# arduino_phc.net
KiCad netlist of a schematic drawn in Altium Designer
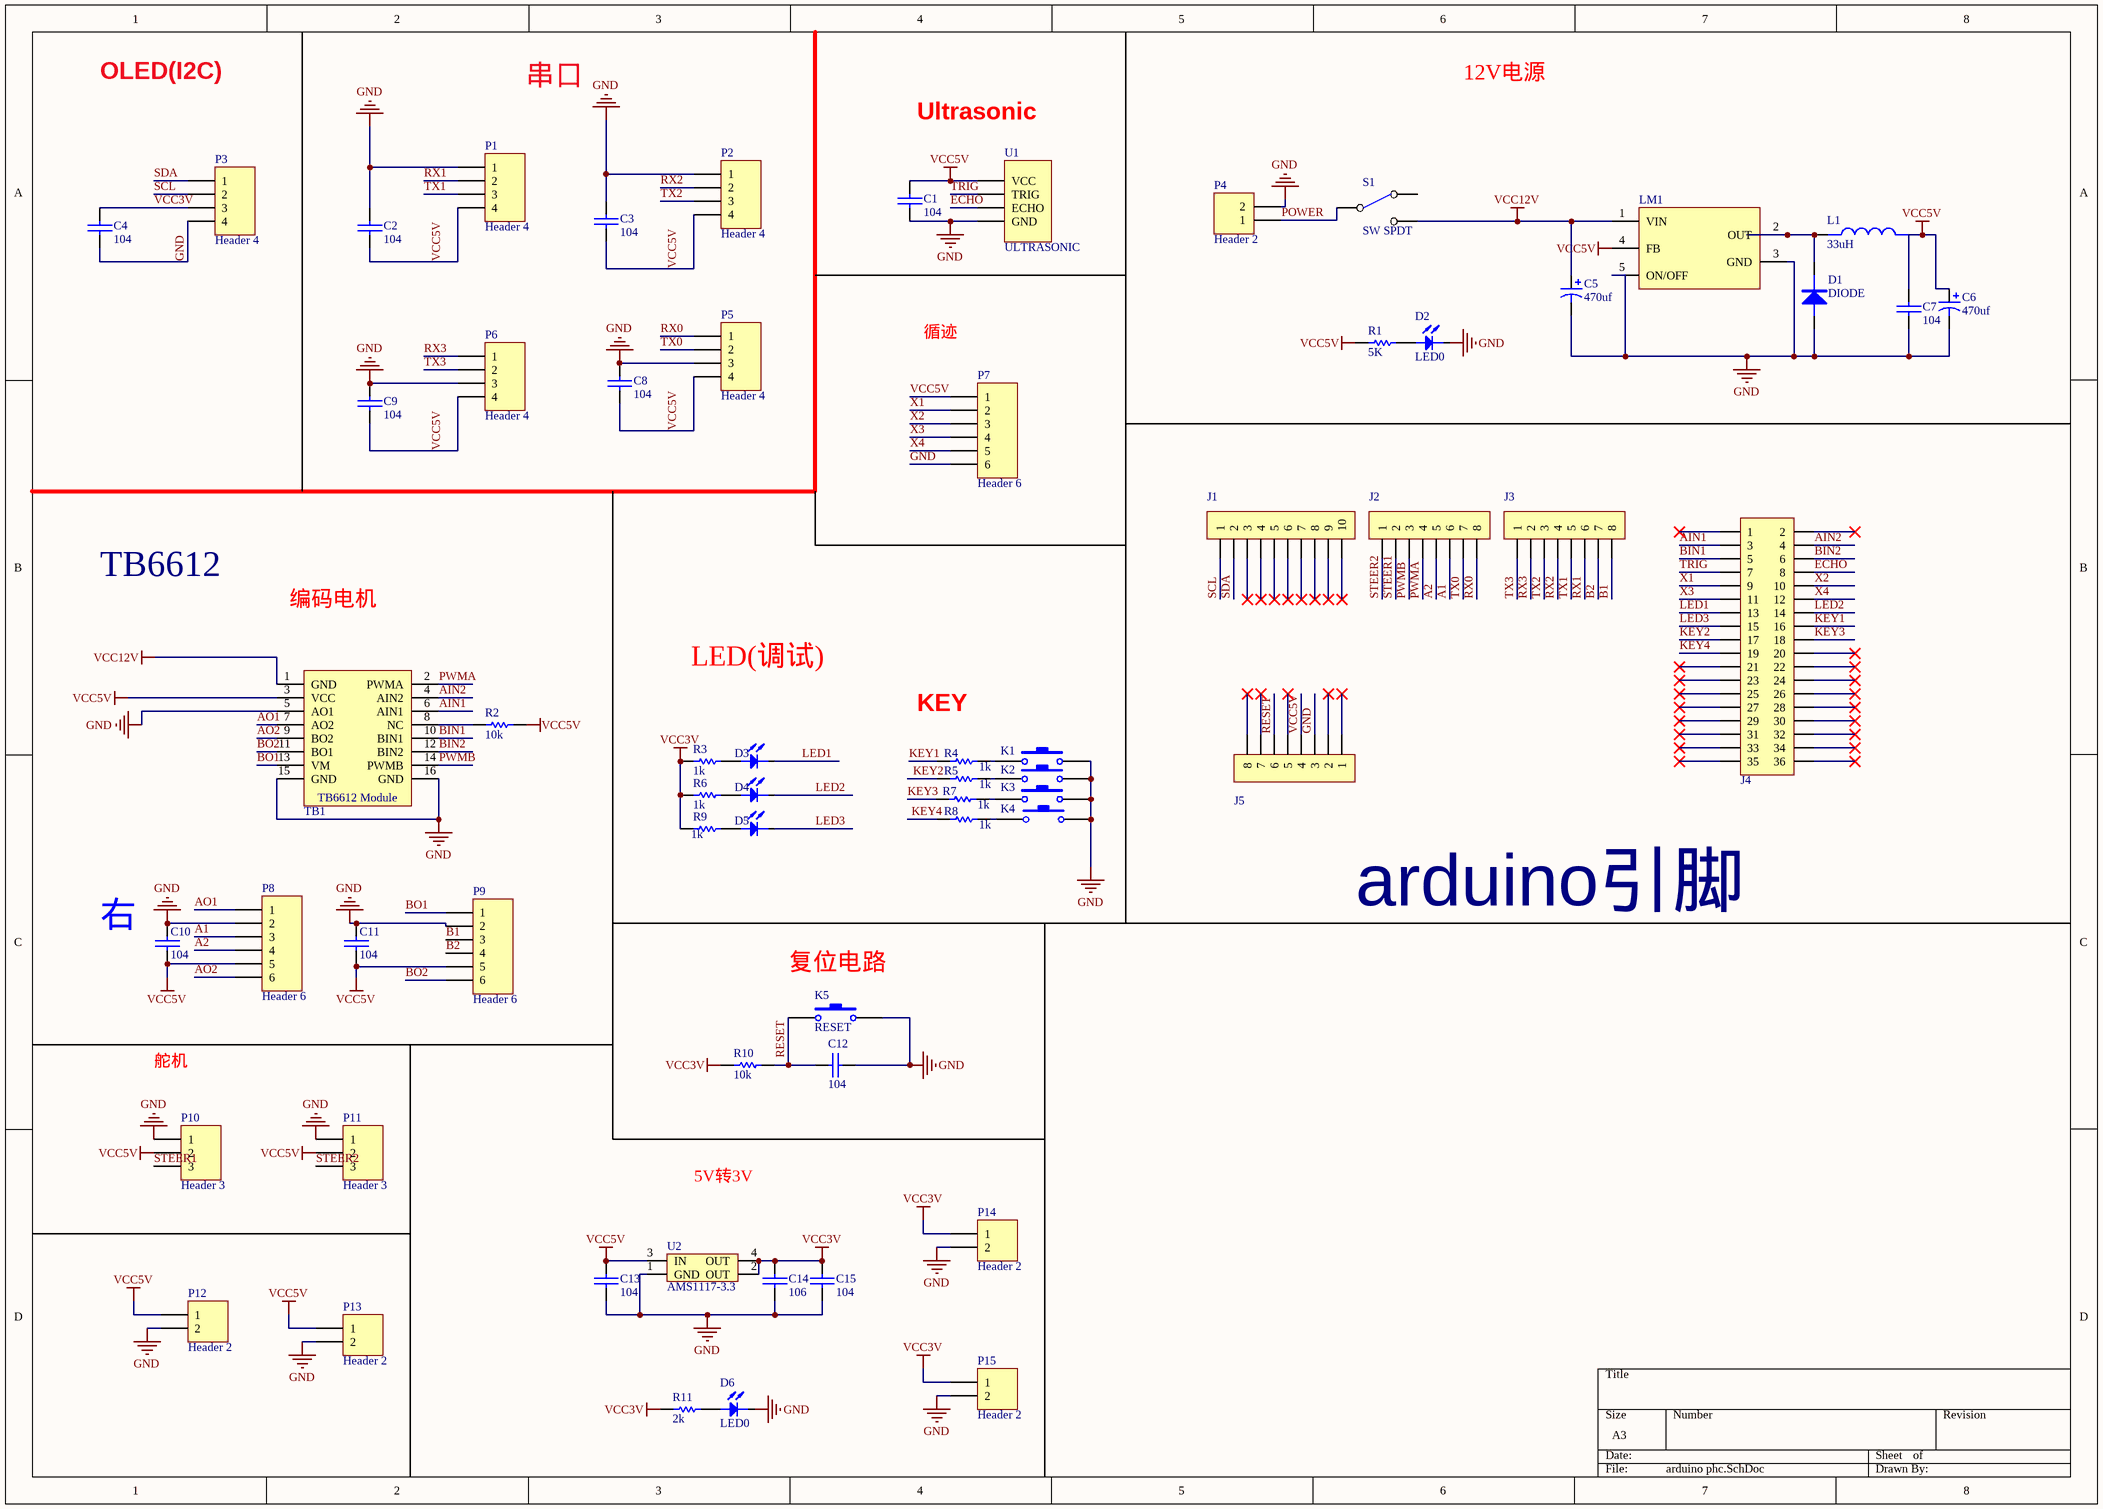
[diagram p0: arduino phc.SchDoc]

(export (version "E")
  (design (tool "Eeschema 10.0.6"))
  (components
    (comp (ref "C1")
      (value "104")
      (footprint "0603_C")
      (fields (field (name "Comment") "CAP"))
      (libsource (lib "MY SCH LIB") (part "CAP"))
    )
    (comp (ref "C2")
      (value "104")
      (footprint "0805_C")
      (fields (field (name "Comment") "CAP"))
      (libsource (lib "MY SCH LIB__JCH") (part "CAP"))
    )
    (comp (ref "C3")
      (value "104")
      (footprint "0805_C")
      (fields (field (name "Comment") "CAP"))
      (libsource (lib "MY SCH LIB__JCH") (part "CAP"))
    )
    (comp (ref "C4")
      (value "104")
      (footprint "0805_C")
      (fields (field (name "Comment") "CAP"))
      (libsource (lib "MY SCH LIB__JCH") (part "CAP"))
    )
    (comp (ref "C5")
      (value "470uf")
      (footprint "CAP-8*16")
      (fields (field (name "Comment") "CAP_HER"))
      (libsource (lib "平衡车") (part "CAP_HER"))
    )
    (comp (ref "C6")
      (value "470uf")
      (footprint "CAP-8*16")
      (fields (field (name "Comment") "CAP_HER"))
      (libsource (lib "平衡车") (part "CAP_HER"))
    )
    (comp (ref "C7")
      (value "104")
      (footprint "0805_C")
      (fields (field (name "Comment") "CAP"))
      (libsource (lib "平衡车") (part "CAP"))
    )
    (comp (ref "C8")
      (value "104")
      (footprint "0805_C")
      (fields (field (name "Comment") "CAP"))
      (libsource (lib "MY SCH LIB__JCH") (part "CAP"))
    )
    (comp (ref "C9")
      (value "104")
      (footprint "0805_C")
      (fields (field (name "Comment") "CAP"))
      (libsource (lib "主控板（32）") (part "CAP"))
    )
    (comp (ref "C10")
      (value "104")
      (footprint "0805_C")
      (fields (field (name "Comment") "CAP"))
      (libsource (lib "MY SCH LIB") (part "CAP"))
    )
    (comp (ref "C11")
      (value "104")
      (footprint "0805_C")
      (fields (field (name "Comment") "CAP"))
      (libsource (lib "MY SCH LIB") (part "CAP"))
    )
    (comp (ref "C12") (value "104") (footprint "0805_C") (libsource (lib "主控板（32）") (part "CAP")))
    (comp (ref "C13")
      (value "104")
      (footprint "0805_C")
      (fields (field (name "Comment") "CAP"))
      (libsource (lib "主控板（32）") (part "CAP"))
    )
    (comp (ref "C14")
      (value "106")
      (footprint "0805_C")
      (fields (field (name "Comment") "CAP"))
      (libsource (lib "主控板（32）") (part "CAP"))
    )
    (comp (ref "C15")
      (value "104")
      (footprint "0805_C")
      (fields (field (name "Comment") "CAP"))
      (libsource (lib "主控板（32）") (part "CAP"))
    )
    (comp (ref "D1") (value "DIODE") (footprint "D1810") (libsource (lib "MY SCH LIB") (part "DIODE")))
    (comp (ref "D2") (value "LED0") (footprint "0805-LED-RED") (libsource (lib "主控板（32）") (part "LED")))
    (comp (ref "D3") (value "LED") (footprint "0805-LED-RED") (libsource (lib "MY SCH LIB") (part "LED")))
    (comp (ref "D4") (value "LED") (footprint "0805-LED-RED") (libsource (lib "MY SCH LIB") (part "LED")))
    (comp (ref "D5") (value "LED") (footprint "0805-LED-RED") (libsource (lib "MY SCH LIB") (part "LED")))
    (comp (ref "D6") (value "LED0") (footprint "0805-LED-RED") (libsource (lib "主控板（32）") (part "LED")))
    (comp (ref "J1")
      (value "HDR-1X10")
      (footprint "HDR2.54-LI-10P")
      (description "10P接插件")
      (libsource (lib "*") (part "Header 10"))
    )
    (comp (ref "J2")
      (value "HDR-1X8")
      (footprint "HDR2.54-LI-8P")
      (description "8P接插件")
      (libsource (lib "") (part "Header 8_1"))
    )
    (comp (ref "J3")
      (value "HDR-1X8")
      (footprint "HDR2.54-LI-8P")
      (description "8P接插件")
      (libsource (lib "") (part "Header 8_1"))
    )
    (comp (ref "J4")
      (value "Header 2X11")
      (footprint "HDR2.54-LI-2x18P")
      (description "18*2P接插件")
      (libsource (lib "arduino扩展版") (part "Header 18X2"))
    )
    (comp (ref "J5")
      (value "HDR-1X8")
      (footprint "HDR2.54-LI-8P")
      (description "8P接插件")
      (libsource (lib "arduino扩展版") (part "Header 8"))
    )
    (comp (ref "K1") (value "KEY2") (footprint "KEY-SMD") (libsource (lib "MY SCH LIB") (part "KEY")))
    (comp (ref "K2") (value "KEY2") (footprint "KEY-SMD") (libsource (lib "MY SCH LIB") (part "KEY")))
    (comp (ref "K3") (value "KEY3") (footprint "KEY-SMD") (libsource (lib "MY SCH LIB") (part "KEY")))
    (comp (ref "K4") (value "KEY3") (footprint "KEY-SMD") (libsource (lib "MY SCH LIB") (part "KEY")))
    (comp (ref "K5") (value "RESET") (footprint "KEY-SMD") (libsource (lib "MY SCH LIB") (part "KEY")))
    (comp (ref "L1") (value "33uH") (footprint "L_SOP74") (libsource (lib "平衡车") (part "IND")))
    (comp (ref "LM1")
      (value "LM2596")
      (footprint "TO-263-5L")
      (description "LM2576")
      (libsource (lib "平衡车") (part "LM2596"))
    )
    (comp (ref "P1")
      (value "Header 4")
      (footprint "HDR1X4")
      (description "Header, 4-Pin")
      (fields (field (name "PUBLISHER") "Altium Limited"))
      (libsource (lib "主控板（32）") (part "Header 4"))
    )
    (comp (ref "P2")
      (value "Header 4")
      (footprint "HDR1X4")
      (description "Header, 4-Pin")
      (fields (field (name "PUBLISHER") "Altium Limited"))
      (libsource (lib "主控板（32）") (part "Header 4"))
    )
    (comp (ref "P3")
      (value "Header 4")
      (footprint "HDR1X4")
      (description "Header, 4-Pin")
      (fields (field (name "PUBLISHER") "Altium Limited"))
      (libsource (lib "主控板（32）") (part "Header 4"))
    )
    (comp (ref "P4")
      (value "Header 2")
      (footprint "DG1282-5.0")
      (description "Header, 2-Pin")
      (fields (field (name "PUBLISHER") "Altium Limited"))
      (libsource (lib "MY SCH LIB") (part "Header 2"))
    )
    (comp (ref "P5")
      (value "Header 4")
      (footprint "HDR1X4")
      (description "Header, 4-Pin")
      (fields (field (name "PUBLISHER") "Altium Limited"))
      (libsource (lib "主控板（32）") (part "Header 4"))
    )
    (comp (ref "P6")
      (value "Header 4")
      (footprint "HDR1X4")
      (description "Header, 4-Pin")
      (fields (field (name "PUBLISHER") "Altium Limited"))
      (libsource (lib "主控板（32）") (part "Header 4"))
    )
    (comp (ref "P7")
      (value "Header 6")
      (footprint "HDR1X6")
      (description "Header, 6-Pin")
      (fields (field (name "PUBLISHER") "Altium Limited"))
      (libsource (lib "MY SCH LIB") (part "Header 6"))
    )
    (comp (ref "P8")
      (value "Header 6")
      (footprint "XH2.54-WS-6P")
      (description "Header, 6-Pin")
      (fields (field (name "PUBLISHER") "Altium Limited"))
      (libsource (lib "MY SCH LIB") (part "Header 6"))
    )
    (comp (ref "P9")
      (value "Header 6")
      (footprint "XH2.54-WS-6P")
      (description "Header, 6-Pin")
      (fields (field (name "PUBLISHER") "Altium Limited"))
      (libsource (lib "MY SCH LIB") (part "Header 6"))
    )
    (comp (ref "P10")
      (value "Header 3")
      (footprint "HDR1X3")
      (description "Header, 3-Pin")
      (fields (field (name "PUBLISHER") "Altium Limited"))
      (libsource (lib "MY SCH LIB") (part "Header 3"))
    )
    (comp (ref "P11")
      (value "Header 3")
      (footprint "HDR1X3")
      (description "Header, 3-Pin")
      (fields (field (name "PUBLISHER") "Altium Limited"))
      (libsource (lib "MY SCH LIB") (part "Header 3"))
    )
    (comp (ref "P12")
      (value "Header 2")
      (footprint "HDR1X2")
      (description "Header, 2-Pin")
      (fields (field (name "PUBLISHER") "Altium Limited"))
      (libsource (lib "主控板（32）") (part "Header 2"))
    )
    (comp (ref "P13")
      (value "Header 2")
      (footprint "HDR1X2")
      (description "Header, 2-Pin")
      (fields (field (name "PUBLISHER") "Altium Limited"))
      (libsource (lib "主控板（32）") (part "Header 2"))
    )
    (comp (ref "P14")
      (value "Header 2")
      (footprint "HDR1X2")
      (description "Header, 2-Pin")
      (fields (field (name "PUBLISHER") "Altium Limited"))
      (libsource (lib "主控板（32）") (part "Header 2"))
    )
    (comp (ref "P15")
      (value "Header 2")
      (footprint "HDR1X2")
      (description "Header, 2-Pin")
      (fields (field (name "PUBLISHER") "Altium Limited"))
      (libsource (lib "主控板（32）") (part "Header 2"))
    )
    (comp (ref "R1") (value "5K") (footprint "0805_R") (libsource (lib "从驱2") (part "RES_1")))
    (comp (ref "R2")
      (value "10k")
      (footprint "0805_R")
      (fields (field (name "Comment") "RES"))
      (libsource (lib "MY SCH LIB") (part "RES"))
    )
    (comp (ref "R3")
      (value "1k")
      (footprint "0805_R")
      (fields (field (name "Comment") "RES"))
      (libsource (lib "MY SCH LIB") (part "RES"))
    )
    (comp (ref "R4")
      (value "1k")
      (footprint "0805_R")
      (fields (field (name "Comment") "RES"))
      (libsource (lib "MY SCH LIB") (part "RES"))
    )
    (comp (ref "R5")
      (value "1k")
      (footprint "0805_R")
      (fields (field (name "Comment") "RES"))
      (libsource (lib "MY SCH LIB") (part "RES"))
    )
    (comp (ref "R6")
      (value "1k")
      (footprint "0805_R")
      (fields (field (name "Comment") "RES"))
      (libsource (lib "MY SCH LIB") (part "RES"))
    )
    (comp (ref "R7")
      (value "1k")
      (footprint "0805_R")
      (fields (field (name "Comment") "RES"))
      (libsource (lib "MY SCH LIB") (part "RES"))
    )
    (comp (ref "R8")
      (value "1k")
      (footprint "0805_R")
      (fields (field (name "Comment") "RES"))
      (libsource (lib "MY SCH LIB") (part "RES"))
    )
    (comp (ref "R9")
      (value "1k")
      (footprint "0805_R")
      (fields (field (name "Comment") "RES"))
      (libsource (lib "MY SCH LIB") (part "RES"))
    )
    (comp (ref "R10")
      (value "RES")
      (footprint "0805_R")
      (fields (field (name "ALTIUM_UNNAMED_1") "10k"))
      (libsource (lib "MY SCH LIB") (part "RES"))
    )
    (comp (ref "R11")
      (value "2k")
      (footprint "0805_R")
      (fields (field (name "Comment") "RES"))
      (libsource (lib "主控板（32）") (part "RES"))
    )
    (comp (ref "S1")
      (value "SW SPDT")
      (footprint "SWITCH_3F_SPDT - 4.7mm")
      (libsource (lib "MY SCH LIB") (part "SW SPDT"))
    )
    (comp (ref "TB1")
      (value "TB6612 Module")
      (footprint "TB6612")
      (fields (field (name "PUBLISHER") "Altium Limited"))
      (libsource (lib "MY SCH LIB") (part "TB6612 Module"))
    )
    (comp (ref "U1")
      (value "ULTRASONIC")
      (footprint "HDR1X4")
      (description "Header, 4-Pin")
      (fields (field (name "PUBLISHER") "Altium Limited"))
      (libsource (lib "从3.0schdoc (1)") (part "ULTRASONIC"))
    )
    (comp (ref "U2")
      (value "AMS1117-3.3")
      (footprint "SOT223_L")
      (libsource (lib "主控板（32）") (part "AMS1117"))
    )
  )
  (nets
    (net (code "1") (name "/A1") (class "Default")
      (node (ref "J2") (pin "6") (pinfunction "6_6") (pintype "passive"))
      (node (ref "P8") (pin "3") (pinfunction "3_3") (pintype "passive"))
    )
    (net (code "2") (name "/A2") (class "Default")
      (node (ref "J2") (pin "5") (pinfunction "5_5") (pintype "passive"))
      (node (ref "P8") (pin "4") (pinfunction "4_4") (pintype "passive"))
    )
    (net (code "3") (name "/AIN1") (class "Default")
      (node (ref "J4") (pin "3") (pinfunction "3_3") (pintype "passive"))
      (node (ref "TB1") (pin "6") (pinfunction "AIN1_6") (pintype "passive"))
    )
    (net (code "4") (name "/AIN2") (class "Default")
      (node (ref "J4") (pin "4") (pinfunction "4_4") (pintype "passive"))
      (node (ref "TB1") (pin "4") (pinfunction "AIN2_4") (pintype "passive"))
    )
    (net (code "5") (name "/AO1") (class "Default")
      (node (ref "P8") (pin "1") (pinfunction "1_1") (pintype "passive"))
      (node (ref "TB1") (pin "7") (pinfunction "AO2_7") (pintype "passive"))
    )
    (net (code "6") (name "/AO2") (class "Default")
      (node (ref "P8") (pin "6") (pinfunction "6_6") (pintype "passive"))
      (node (ref "TB1") (pin "9") (pinfunction "BO2_9") (pintype "passive"))
    )
    (net (code "7") (name "/B1") (class "Default")
      (node (ref "J3") (pin "8") (pinfunction "8_8") (pintype "passive"))
      (node (ref "P9") (pin "3") (pinfunction "3_3") (pintype "passive"))
    )
    (net (code "8") (name "/B2") (class "Default")
      (node (ref "J3") (pin "7") (pinfunction "7_7") (pintype "passive"))
      (node (ref "P9") (pin "4") (pinfunction "4_4") (pintype "passive"))
    )
    (net (code "9") (name "/BIN1") (class "Default")
      (node (ref "J4") (pin "5") (pinfunction "5_5") (pintype "passive"))
      (node (ref "TB1") (pin "10") (pinfunction "BIN1_10") (pintype "passive"))
    )
    (net (code "10") (name "/BIN2") (class "Default")
      (node (ref "J4") (pin "6") (pinfunction "6_6") (pintype "passive"))
      (node (ref "TB1") (pin "12") (pinfunction "BIN2_12") (pintype "passive"))
    )
    (net (code "11") (name "/BO1") (class "Default")
      (node (ref "P9") (pin "1") (pinfunction "1_1") (pintype "passive"))
      (node (ref "TB1") (pin "13") (pinfunction "VM_13") (pintype "passive"))
    )
    (net (code "12") (name "/BO2") (class "Default")
      (node (ref "P9") (pin "6") (pinfunction "6_6") (pintype "passive"))
      (node (ref "TB1") (pin "11") (pinfunction "BO1_11") (pintype "passive"))
    )
    (net (code "13") (name "/ECHO") (class "Default")
      (node (ref "J4") (pin "8") (pinfunction "8_8") (pintype "passive"))
      (node (ref "U1") (pin "3") (pinfunction "ECHO_3") (pintype "passive"))
    )
    (net (code "14") (name "/KEY1") (class "Default")
      (node (ref "J4") (pin "16") (pinfunction "16_16") (pintype "passive"))
      (node (ref "R4") (pin "1") (pinfunction "BOT_1") (pintype "passive"))
    )
    (net (code "15") (name "/KEY2") (class "Default")
      (node (ref "J4") (pin "17") (pinfunction "17_17") (pintype "passive"))
      (node (ref "R5") (pin "1") (pinfunction "BOT_1") (pintype "passive"))
    )
    (net (code "16") (name "/KEY3") (class "Default")
      (node (ref "J4") (pin "18") (pinfunction "18_18") (pintype "passive"))
      (node (ref "R7") (pin "1") (pinfunction "BOT_1") (pintype "passive"))
    )
    (net (code "17") (name "/KEY4") (class "Default")
      (node (ref "J4") (pin "19") (pinfunction "19_19") (pintype "passive"))
      (node (ref "R8") (pin "1") (pinfunction "BOT_1") (pintype "passive"))
    )
    (net (code "18") (name "/LED1") (class "Default")
      (node (ref "D3") (pin "K") (pintype "passive"))
      (node (ref "J4") (pin "13") (pinfunction "13_13") (pintype "passive"))
    )
    (net (code "19") (name "/LED2") (class "Default")
      (node (ref "D4") (pin "K") (pintype "passive"))
      (node (ref "J4") (pin "14") (pinfunction "14_14") (pintype "passive"))
    )
    (net (code "20") (name "/LED3") (class "Default")
      (node (ref "D5") (pin "K") (pintype "passive"))
      (node (ref "J4") (pin "15") (pinfunction "15_15") (pintype "passive"))
    )
    (net (code "21") (name "/POWER") (class "Default")
      (node (ref "P4") (pin "1") (pinfunction "1_1") (pintype "passive"))
      (node (ref "S1") (pin "2") (pinfunction "COMMON_2") (pintype "passive"))
    )
    (net (code "22") (name "/PWMA") (class "Default")
      (node (ref "J2") (pin "4") (pinfunction "4_4") (pintype "passive"))
      (node (ref "TB1") (pin "2") (pinfunction "PWMA_2") (pintype "passive"))
    )
    (net (code "23") (name "/PWMB") (class "Default")
      (node (ref "J2") (pin "3") (pinfunction "3_3") (pintype "passive"))
      (node (ref "TB1") (pin "14") (pinfunction "PWMB_14") (pintype "passive"))
    )
    (net (code "24") (name "/RESET") (class "Default")
      (node (ref "C12") (pin "1") (pinfunction "1_1") (pintype "passive"))
      (node (ref "J5") (pin "6") (pinfunction "6_6") (pintype "passive"))
      (node (ref "K5") (pin "1") (pinfunction "1_1") (pintype "passive"))
      (node (ref "R10") (pin "1") (pinfunction "BOT_1") (pintype "passive"))
    )
    (net (code "25") (name "/RX0") (class "Default")
      (node (ref "J2") (pin "8") (pinfunction "8_8") (pintype "passive"))
      (node (ref "P5") (pin "1") (pinfunction "1_1") (pintype "passive"))
    )
    (net (code "26") (name "/RX1") (class "Default")
      (node (ref "J3") (pin "6") (pinfunction "6_6") (pintype "passive"))
      (node (ref "P1") (pin "2") (pinfunction "2_2") (pintype "passive"))
    )
    (net (code "27") (name "/RX2") (class "Default")
      (node (ref "J3") (pin "4") (pinfunction "4_4") (pintype "passive"))
      (node (ref "P2") (pin "2") (pinfunction "2_2") (pintype "passive"))
    )
    (net (code "28") (name "/RX3") (class "Default")
      (node (ref "J3") (pin "2") (pinfunction "2_2") (pintype "passive"))
      (node (ref "P6") (pin "1") (pinfunction "1_1") (pintype "passive"))
    )
    (net (code "29") (name "/SCL") (class "Default")
      (node (ref "J1") (pin "1") (pinfunction "1_1") (pintype "passive"))
      (node (ref "P3") (pin "2") (pinfunction "2_2") (pintype "passive"))
    )
    (net (code "30") (name "/SDA") (class "Default")
      (node (ref "J1") (pin "2") (pinfunction "2_2") (pintype "passive"))
      (node (ref "P3") (pin "1") (pinfunction "1_1") (pintype "passive"))
    )
    (net (code "31") (name "/STEER1") (class "Default")
      (node (ref "J2") (pin "2") (pinfunction "2_2") (pintype "passive"))
      (node (ref "P10") (pin "3") (pinfunction "3_3") (pintype "passive"))
    )
    (net (code "32") (name "/STEER2") (class "Default")
      (node (ref "J2") (pin "1") (pinfunction "1_1") (pintype "passive"))
      (node (ref "P11") (pin "3") (pinfunction "3_3") (pintype "passive"))
    )
    (net (code "33") (name "/TRIG") (class "Default")
      (node (ref "J4") (pin "7") (pinfunction "7_7") (pintype "passive"))
      (node (ref "U1") (pin "2") (pinfunction "TRIG_2") (pintype "passive"))
    )
    (net (code "34") (name "/TX0") (class "Default")
      (node (ref "J2") (pin "7") (pinfunction "7_7") (pintype "passive"))
      (node (ref "P5") (pin "2") (pinfunction "2_2") (pintype "passive"))
    )
    (net (code "35") (name "/TX1") (class "Default")
      (node (ref "J3") (pin "5") (pinfunction "5_5") (pintype "passive"))
      (node (ref "P1") (pin "3") (pinfunction "3_3") (pintype "passive"))
    )
    (net (code "36") (name "/TX2") (class "Default")
      (node (ref "J3") (pin "3") (pinfunction "3_3") (pintype "passive"))
      (node (ref "P2") (pin "3") (pinfunction "3_3") (pintype "passive"))
    )
    (net (code "37") (name "/TX3") (class "Default")
      (node (ref "J3") (pin "1") (pinfunction "1_1") (pintype "passive"))
      (node (ref "P6") (pin "2") (pinfunction "2_2") (pintype "passive"))
    )
    (net (code "38") (name "/X1") (class "Default")
      (node (ref "J4") (pin "9") (pinfunction "9_9") (pintype "passive"))
      (node (ref "P7") (pin "2") (pinfunction "2_2") (pintype "passive"))
    )
    (net (code "39") (name "/X2") (class "Default")
      (node (ref "J4") (pin "10") (pinfunction "10_10") (pintype "passive"))
      (node (ref "P7") (pin "3") (pinfunction "3_3") (pintype "passive"))
    )
    (net (code "40") (name "/X3") (class "Default")
      (node (ref "J4") (pin "11") (pinfunction "11_11") (pintype "passive"))
      (node (ref "P7") (pin "4") (pinfunction "4_4") (pintype "passive"))
    )
    (net (code "41") (name "/X4") (class "Default")
      (node (ref "J4") (pin "12") (pinfunction "12_12") (pintype "passive"))
      (node (ref "P7") (pin "5") (pinfunction "5_5") (pintype "passive"))
    )
    (net (code "42") (name "GND") (class "Default")
      (node (ref "C1") (pin "2") (pinfunction "2_2") (pintype "passive"))
      (node (ref "C10") (pin "1") (pinfunction "1_1") (pintype "passive"))
      (node (ref "C11") (pin "1") (pinfunction "1_1") (pintype "passive"))
      (node (ref "C12") (pin "2") (pinfunction "2_2") (pintype "passive"))
      (node (ref "C13") (pin "2") (pinfunction "2_2") (pintype "passive"))
      (node (ref "C14") (pin "2") (pinfunction "2_2") (pintype "passive"))
      (node (ref "C15") (pin "2") (pinfunction "2_2") (pintype "passive"))
      (node (ref "C2") (pin "1") (pinfunction "1_1") (pintype "passive"))
      (node (ref "C3") (pin "1") (pinfunction "1_1") (pintype "passive"))
      (node (ref "C4") (pin "2") (pinfunction "2_2") (pintype "passive"))
      (node (ref "C5") (pin "2") (pinfunction "2_2") (pintype "passive"))
      (node (ref "C6") (pin "2") (pinfunction "2_2") (pintype "passive"))
      (node (ref "C7") (pin "2") (pinfunction "2_2") (pintype "passive"))
      (node (ref "C8") (pin "1") (pinfunction "1_1") (pintype "passive"))
      (node (ref "C9") (pin "1") (pinfunction "1_1") (pintype "passive"))
      (node (ref "D1") (pin "a") (pintype "passive"))
      (node (ref "D2") (pin "K") (pintype "passive"))
      (node (ref "D6") (pin "K") (pintype "passive"))
      (node (ref "J5") (pin "3") (pinfunction "3_3") (pintype "passive"))
      (node (ref "K1") (pin "2") (pinfunction "2_2") (pintype "passive"))
      (node (ref "K2") (pin "2") (pinfunction "2_2") (pintype "passive"))
      (node (ref "K3") (pin "2") (pinfunction "2_2") (pintype "passive"))
      (node (ref "K4") (pin "2") (pinfunction "2_2") (pintype "passive"))
      (node (ref "K5") (pin "2") (pinfunction "2_2") (pintype "passive"))
      (node (ref "LM1") (pin "3") (pinfunction "GND_3") (pintype "passive"))
      (node (ref "LM1") (pin "5") (pinfunction "ON/OFF_5") (pintype "passive"))
      (node (ref "P1") (pin "1") (pinfunction "1_1") (pintype "passive"))
      (node (ref "P10") (pin "1") (pinfunction "1_1") (pintype "passive"))
      (node (ref "P11") (pin "1") (pinfunction "1_1") (pintype "passive"))
      (node (ref "P12") (pin "2") (pinfunction "2_2") (pintype "passive"))
      (node (ref "P13") (pin "2") (pinfunction "2_2") (pintype "passive"))
      (node (ref "P14") (pin "2") (pinfunction "2_2") (pintype "passive"))
      (node (ref "P15") (pin "2") (pinfunction "2_2") (pintype "passive"))
      (node (ref "P2") (pin "1") (pinfunction "1_1") (pintype "passive"))
      (node (ref "P3") (pin "4") (pinfunction "4_4") (pintype "passive"))
      (node (ref "P4") (pin "2") (pinfunction "2_2") (pintype "passive"))
      (node (ref "P5") (pin "3") (pinfunction "3_3") (pintype "passive"))
      (node (ref "P6") (pin "3") (pinfunction "3_3") (pintype "passive"))
      (node (ref "P7") (pin "6") (pinfunction "6_6") (pintype "passive"))
      (node (ref "P8") (pin "2") (pinfunction "2_2") (pintype "passive"))
      (node (ref "P9") (pin "2") (pinfunction "2_2") (pintype "passive"))
      (node (ref "TB1") (pin "15") (pinfunction "GND_15") (pintype "passive"))
      (node (ref "TB1") (pin "16") (pinfunction "GND_16") (pintype "passive"))
      (node (ref "TB1") (pin "5") (pinfunction "AO1_5") (pintype "passive"))
      (node (ref "U1") (pin "4") (pinfunction "GND_4") (pintype "passive"))
      (node (ref "U2") (pin "1") (pinfunction "GND_1") (pintype "passive"))
    )
    (net (code "43") (name "Net-(LM1-OUT)") (class "Default")
      (node (ref "D1") (pin "K") (pintype "passive"))
      (node (ref "L1") (pin "1") (pinfunction "Pri-_1") (pintype "passive"))
      (node (ref "LM1") (pin "2") (pinfunction "OUT_2") (pintype "passive"))
    )
    (net (code "44") (name "Net-(R1-TOP)") (class "Default")
      (node (ref "D2") (pin "A") (pintype "passive"))
      (node (ref "R1") (pin "2") (pinfunction "TOP_2") (pintype "passive"))
    )
    (net (code "45") (name "Net-(R2-TOP)") (class "Default")
      (node (ref "R2") (pin "2") (pinfunction "TOP_2") (pintype "passive"))
      (node (ref "TB1") (pin "8") (pinfunction "NC_8") (pintype "passive"))
    )
    (net (code "46") (name "Net-(R3-TOP)") (class "Default")
      (node (ref "D3") (pin "A") (pintype "passive"))
      (node (ref "R3") (pin "2") (pinfunction "TOP_2") (pintype "passive"))
    )
    (net (code "47") (name "Net-(R4-TOP)") (class "Default")
      (node (ref "K1") (pin "1") (pinfunction "1_1") (pintype "passive"))
      (node (ref "R4") (pin "2") (pinfunction "TOP_2") (pintype "passive"))
    )
    (net (code "48") (name "Net-(R5-TOP)") (class "Default")
      (node (ref "K2") (pin "1") (pinfunction "1_1") (pintype "passive"))
      (node (ref "R5") (pin "2") (pinfunction "TOP_2") (pintype "passive"))
    )
    (net (code "49") (name "Net-(R6-TOP)") (class "Default")
      (node (ref "D4") (pin "A") (pintype "passive"))
      (node (ref "R6") (pin "2") (pinfunction "TOP_2") (pintype "passive"))
    )
    (net (code "50") (name "Net-(R7-TOP)") (class "Default")
      (node (ref "K3") (pin "1") (pinfunction "1_1") (pintype "passive"))
      (node (ref "R7") (pin "2") (pinfunction "TOP_2") (pintype "passive"))
    )
    (net (code "51") (name "Net-(R8-TOP)") (class "Default")
      (node (ref "K4") (pin "1") (pinfunction "1_1") (pintype "passive"))
      (node (ref "R8") (pin "2") (pinfunction "TOP_2") (pintype "passive"))
    )
    (net (code "52") (name "Net-(R9-TOP)") (class "Default")
      (node (ref "D5") (pin "A") (pintype "passive"))
      (node (ref "R9") (pin "2") (pinfunction "TOP_2") (pintype "passive"))
    )
    (net (code "53") (name "Net-(R11-TOP)") (class "Default")
      (node (ref "D6") (pin "A") (pintype "passive"))
      (node (ref "R11") (pin "2") (pinfunction "TOP_2") (pintype "passive"))
    )
    (net (code "54") (name "VCC3V") (class "Default")
      (node (ref "C14") (pin "1") (pinfunction "1_1") (pintype "passive"))
      (node (ref "C15") (pin "1") (pinfunction "1_1") (pintype "passive"))
      (node (ref "C4") (pin "1") (pinfunction "1_1") (pintype "passive"))
      (node (ref "P14") (pin "1") (pinfunction "1_1") (pintype "passive"))
      (node (ref "P15") (pin "1") (pinfunction "1_1") (pintype "passive"))
      (node (ref "P3") (pin "3") (pinfunction "3_3") (pintype "passive"))
      (node (ref "R10") (pin "2") (pinfunction "TOP_2") (pintype "passive"))
      (node (ref "R11") (pin "1") (pinfunction "BOT_1") (pintype "passive"))
      (node (ref "R3") (pin "1") (pinfunction "BOT_1") (pintype "passive"))
      (node (ref "R6") (pin "1") (pinfunction "BOT_1") (pintype "passive"))
      (node (ref "R9") (pin "1") (pinfunction "BOT_1") (pintype "passive"))
      (node (ref "U2") (pin "2") (pinfunction "OUT_2") (pintype "passive"))
      (node (ref "U2") (pin "4") (pinfunction "OUT_4") (pintype "passive"))
    )
    (net (code "55") (name "VCC5V") (class "Default")
      (node (ref "C1") (pin "1") (pinfunction "1_1") (pintype "passive"))
      (node (ref "C10") (pin "2") (pinfunction "2_2") (pintype "passive"))
      (node (ref "C11") (pin "2") (pinfunction "2_2") (pintype "passive"))
      (node (ref "C13") (pin "1") (pinfunction "1_1") (pintype "passive"))
      (node (ref "C2") (pin "2") (pinfunction "2_2") (pintype "passive"))
      (node (ref "C3") (pin "2") (pinfunction "2_2") (pintype "passive"))
      (node (ref "C6") (pin "1") (pinfunction "1_1") (pintype "passive"))
      (node (ref "C7") (pin "1") (pinfunction "1_1") (pintype "passive"))
      (node (ref "C8") (pin "2") (pinfunction "2_2") (pintype "passive"))
      (node (ref "C9") (pin "2") (pinfunction "2_2") (pintype "passive"))
      (node (ref "J5") (pin "4") (pinfunction "4_4") (pintype "passive"))
      (node (ref "L1") (pin "2") (pinfunction "Pri-_2") (pintype "passive"))
      (node (ref "LM1") (pin "4") (pinfunction "FB_4") (pintype "passive"))
      (node (ref "P1") (pin "4") (pinfunction "4_4") (pintype "passive"))
      (node (ref "P10") (pin "2") (pinfunction "2_2") (pintype "passive"))
      (node (ref "P11") (pin "2") (pinfunction "2_2") (pintype "passive"))
      (node (ref "P12") (pin "1") (pinfunction "1_1") (pintype "passive"))
      (node (ref "P13") (pin "1") (pinfunction "1_1") (pintype "passive"))
      (node (ref "P2") (pin "4") (pinfunction "4_4") (pintype "passive"))
      (node (ref "P5") (pin "4") (pinfunction "4_4") (pintype "passive"))
      (node (ref "P6") (pin "4") (pinfunction "4_4") (pintype "passive"))
      (node (ref "P7") (pin "1") (pinfunction "1_1") (pintype "passive"))
      (node (ref "P8") (pin "5") (pinfunction "5_5") (pintype "passive"))
      (node (ref "P9") (pin "5") (pinfunction "5_5") (pintype "passive"))
      (node (ref "R1") (pin "1") (pinfunction "BOT_1") (pintype "passive"))
      (node (ref "R2") (pin "1") (pinfunction "BOT_1") (pintype "passive"))
      (node (ref "TB1") (pin "3") (pinfunction "VCC_3") (pintype "passive"))
      (node (ref "U1") (pin "1") (pinfunction "VCC_1") (pintype "passive"))
      (node (ref "U2") (pin "3") (pinfunction "IN_3") (pintype "passive"))
    )
    (net (code "56") (name "VCC12V") (class "Default")
      (node (ref "C5") (pin "1") (pinfunction "1_1") (pintype "passive"))
      (node (ref "LM1") (pin "1") (pinfunction "VIN_1") (pintype "passive"))
      (node (ref "S1") (pin "3") (pinfunction "NO_3") (pintype "passive"))
      (node (ref "TB1") (pin "1") (pinfunction "GND_1") (pintype "passive"))
    )
    (net (code "57") (name "unconnected-(J1-Pad3)") (class "Default")
      (node (ref "J1") (pin "3") (pinfunction "3_3") (pintype "passive+no_connect"))
    )
    (net (code "58") (name "unconnected-(J1-Pad4)") (class "Default")
      (node (ref "J1") (pin "4") (pinfunction "4_4") (pintype "passive+no_connect"))
    )
    (net (code "59") (name "unconnected-(J1-Pad5)") (class "Default")
      (node (ref "J1") (pin "5") (pinfunction "5_5") (pintype "passive+no_connect"))
    )
    (net (code "60") (name "unconnected-(J1-Pad6)") (class "Default")
      (node (ref "J1") (pin "6") (pinfunction "6_6") (pintype "passive+no_connect"))
    )
    (net (code "61") (name "unconnected-(J1-Pad7)") (class "Default")
      (node (ref "J1") (pin "7") (pinfunction "7_7") (pintype "passive+no_connect"))
    )
    (net (code "62") (name "unconnected-(J1-Pad8)") (class "Default")
      (node (ref "J1") (pin "8") (pinfunction "8_8") (pintype "passive+no_connect"))
    )
    (net (code "63") (name "unconnected-(J1-Pad9)") (class "Default")
      (node (ref "J1") (pin "9") (pinfunction "9_9") (pintype "passive+no_connect"))
    )
    (net (code "64") (name "unconnected-(J1-Pad10)") (class "Default")
      (node (ref "J1") (pin "10") (pinfunction "10_10") (pintype "passive+no_connect"))
    )
    (net (code "65") (name "unconnected-(J4-Pad1)") (class "Default")
      (node (ref "J4") (pin "1") (pinfunction "1_1") (pintype "passive+no_connect"))
    )
    (net (code "66") (name "unconnected-(J4-Pad2)") (class "Default")
      (node (ref "J4") (pin "2") (pinfunction "2_2") (pintype "passive+no_connect"))
    )
    (net (code "67") (name "unconnected-(J4-Pad20)") (class "Default")
      (node (ref "J4") (pin "20") (pinfunction "20_20") (pintype "passive+no_connect"))
    )
    (net (code "68") (name "unconnected-(J4-Pad21)") (class "Default")
      (node (ref "J4") (pin "21") (pinfunction "21_21") (pintype "passive+no_connect"))
    )
    (net (code "69") (name "unconnected-(J4-Pad22)") (class "Default")
      (node (ref "J4") (pin "22") (pinfunction "22_22") (pintype "passive+no_connect"))
    )
    (net (code "70") (name "unconnected-(J4-Pad23)") (class "Default")
      (node (ref "J4") (pin "23") (pinfunction "23_23") (pintype "passive+no_connect"))
    )
    (net (code "71") (name "unconnected-(J4-Pad24)") (class "Default")
      (node (ref "J4") (pin "24") (pinfunction "24_24") (pintype "passive+no_connect"))
    )
    (net (code "72") (name "unconnected-(J4-Pad25)") (class "Default")
      (node (ref "J4") (pin "25") (pinfunction "25_25") (pintype "passive+no_connect"))
    )
    (net (code "73") (name "unconnected-(J4-Pad26)") (class "Default")
      (node (ref "J4") (pin "26") (pinfunction "26_26") (pintype "passive+no_connect"))
    )
    (net (code "74") (name "unconnected-(J4-Pad27)") (class "Default")
      (node (ref "J4") (pin "27") (pinfunction "27_27") (pintype "passive+no_connect"))
    )
    (net (code "75") (name "unconnected-(J4-Pad28)") (class "Default")
      (node (ref "J4") (pin "28") (pinfunction "28_28") (pintype "passive+no_connect"))
    )
    (net (code "76") (name "unconnected-(J4-Pad29)") (class "Default")
      (node (ref "J4") (pin "29") (pinfunction "29_29") (pintype "passive+no_connect"))
    )
    (net (code "77") (name "unconnected-(J4-Pad30)") (class "Default")
      (node (ref "J4") (pin "30") (pinfunction "30_30") (pintype "passive+no_connect"))
    )
    (net (code "78") (name "unconnected-(J4-Pad31)") (class "Default")
      (node (ref "J4") (pin "31") (pinfunction "31_31") (pintype "passive+no_connect"))
    )
    (net (code "79") (name "unconnected-(J4-Pad32)") (class "Default")
      (node (ref "J4") (pin "32") (pinfunction "32_32") (pintype "passive+no_connect"))
    )
    (net (code "80") (name "unconnected-(J4-Pad33)") (class "Default")
      (node (ref "J4") (pin "33") (pinfunction "33_33") (pintype "passive+no_connect"))
    )
    (net (code "81") (name "unconnected-(J4-Pad34)") (class "Default")
      (node (ref "J4") (pin "34") (pinfunction "34_34") (pintype "passive+no_connect"))
    )
    (net (code "82") (name "unconnected-(J4-Pad35)") (class "Default")
      (node (ref "J4") (pin "35") (pinfunction "35_35") (pintype "passive+no_connect"))
    )
    (net (code "83") (name "unconnected-(J4-Pad36)") (class "Default")
      (node (ref "J4") (pin "36") (pinfunction "36_36") (pintype "passive+no_connect"))
    )
    (net (code "84") (name "unconnected-(J5-Pad1)") (class "Default")
      (node (ref "J5") (pin "1") (pinfunction "1_1") (pintype "passive+no_connect"))
    )
    (net (code "85") (name "unconnected-(J5-Pad2)") (class "Default")
      (node (ref "J5") (pin "2") (pinfunction "2_2") (pintype "passive+no_connect"))
    )
    (net (code "86") (name "unconnected-(J5-Pad5)") (class "Default")
      (node (ref "J5") (pin "5") (pinfunction "5_5") (pintype "passive+no_connect"))
    )
    (net (code "87") (name "unconnected-(J5-Pad7)") (class "Default")
      (node (ref "J5") (pin "7") (pinfunction "7_7") (pintype "passive+no_connect"))
    )
    (net (code "88") (name "unconnected-(J5-Pad8)") (class "Default")
      (node (ref "J5") (pin "8") (pinfunction "8_8") (pintype "passive+no_connect"))
    )
    (net (code "89") (name "unconnected-(S1-NC-Pad1)") (class "Default")
      (node (ref "S1") (pin "1") (pinfunction "NC_1") (pintype "passive"))
    )
  )
)
